# PCB_OPTO_FAST.net
KiCad netlist of a schematic drawn in Altium Designer
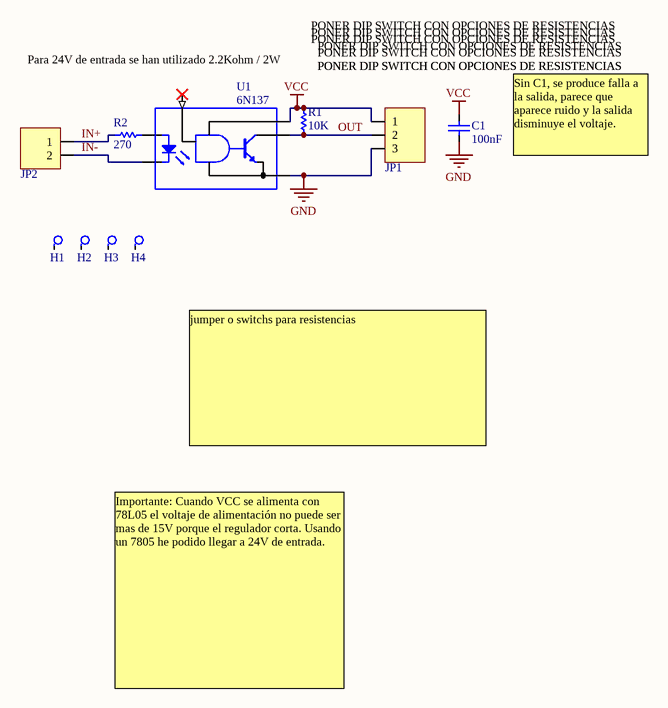
[diagram p0: PCB OPTO FAST.SchDoc]

(export (version "E")
  (design (tool "Eeschema 10.0.6"))
  (components
    (comp (ref "C1")
      (value "Capacitor 1206; 100nF; 50V")
      (footprint "C1206")
      (fields (field (name "CAPACIDAD") "100nF"))
      (libsource (lib "FEDE") (part "Capacitor 1206; 100nF; 50V"))
    )
    (comp (ref "H1")
      (value "Agujero de Montaje")
      (footprint "agujero")
      (libsource (lib "FEDE") (part "Agujero de Montaje"))
    )
    (comp (ref "H2")
      (value "Agujero de Montaje")
      (footprint "agujero")
      (libsource (lib "FEDE") (part "Agujero de Montaje"))
    )
    (comp (ref "H3")
      (value "Agujero de Montaje")
      (footprint "agujero")
      (libsource (lib "FEDE") (part "Agujero de Montaje"))
    )
    (comp (ref "H4")
      (value "Agujero de Montaje")
      (footprint "agujero")
      (libsource (lib "FEDE") (part "Agujero de Montaje"))
    )
    (comp (ref "JP1")
      (value "Header3x1")
      (footprint "conpol3x1")
      (description "Header 3x1")
      (libsource (lib "FEDE") (part "Header3x1"))
    )
    (comp (ref "JP2")
      (value "Header2x1")
      (footprint "CONPOL2X1")
      (description "Header 2x1")
      (libsource (lib "FEDE") (part "Header2x1"))
    )
    (comp (ref "R1")
      (value "10K")
      (footprint "R1206")
      (description "Resistor")
      (fields (field (name "POWER") "0.25W") (field (name "Comment") "Res"))
      (libsource (lib "FEDE") (part "Res"))
    )
    (comp (ref "R2")
      (value "270")
      (footprint "R1206")
      (description "Resistor")
      (fields (field (name "POWER") "0.25W") (field (name "Comment") "Res"))
      (libsource (lib "FEDE") (part "Res"))
    )
    (comp (ref "U1")
      (value "6N137")
      (footprint "DIP8Z")
      (description "Optoaislador")
      (libsource (lib "FEDE") (part "6N137"))
    )
  )
  (nets
    (net (code "1") (name "/IN+") (class "Default")
      (node (ref "JP2") (pin "1") (pinfunction "1_1") (pintype "passive"))
      (node (ref "R2") (pin "1") (pinfunction "1_1") (pintype "passive"))
    )
    (net (code "2") (name "/IN-") (class "Default")
      (node (ref "JP2") (pin "2") (pinfunction "2_2") (pintype "passive"))
      (node (ref "U1") (pin "3") (pinfunction "K_3") (pintype "passive"))
    )
    (net (code "3") (name "/OUT") (class "Default")
      (node (ref "JP1") (pin "2") (pinfunction "2_2") (pintype "passive"))
      (node (ref "R1") (pin "1") (pinfunction "1_1") (pintype "passive"))
      (node (ref "U1") (pin "6") (pinfunction "VO_6") (pintype "open_collector"))
    )
    (net (code "4") (name "GND") (class "Default")
      (node (ref "C1") (pin "1") (pinfunction "1_1") (pintype "passive"))
      (node (ref "JP1") (pin "3") (pinfunction "3_3") (pintype "passive"))
      (node (ref "U1") (pin "5") (pinfunction "GND_5") (pintype "power_in"))
    )
    (net (code "5") (name "Net-(U1-A)") (class "Default")
      (node (ref "R2") (pin "2") (pinfunction "2_2") (pintype "passive"))
      (node (ref "U1") (pin "2") (pinfunction "A_2") (pintype "passive"))
    )
    (net (code "6") (name "VCC") (class "Default")
      (node (ref "C1") (pin "2") (pinfunction "2_2") (pintype "passive"))
      (node (ref "JP1") (pin "1") (pinfunction "1_1") (pintype "passive"))
      (node (ref "R1") (pin "2") (pinfunction "2_2") (pintype "passive"))
      (node (ref "U1") (pin "8") (pinfunction "VCC_8") (pintype "power_in"))
    )
    (net (code "7") (name "unconnected-(H1-Pad1)") (class "Default")
      (node (ref "H1") (pin "1") (pinfunction "1_1") (pintype "passive"))
    )
    (net (code "8") (name "unconnected-(H2-Pad1)") (class "Default")
      (node (ref "H2") (pin "1") (pinfunction "1_1") (pintype "passive"))
    )
    (net (code "9") (name "unconnected-(H3-Pad1)") (class "Default")
      (node (ref "H3") (pin "1") (pinfunction "1_1") (pintype "passive"))
    )
    (net (code "10") (name "unconnected-(H4-Pad1)") (class "Default")
      (node (ref "H4") (pin "1") (pinfunction "1_1") (pintype "passive"))
    )
    (net (code "11") (name "unconnected-(U1-VE-Pad7)") (class "Default")
      (node (ref "U1") (pin "7") (pinfunction "VE_7") (pintype "input+no_connect"))
    )
  )
)
